# design.net
KiCad netlist of a schematic drawn in Altium Designer
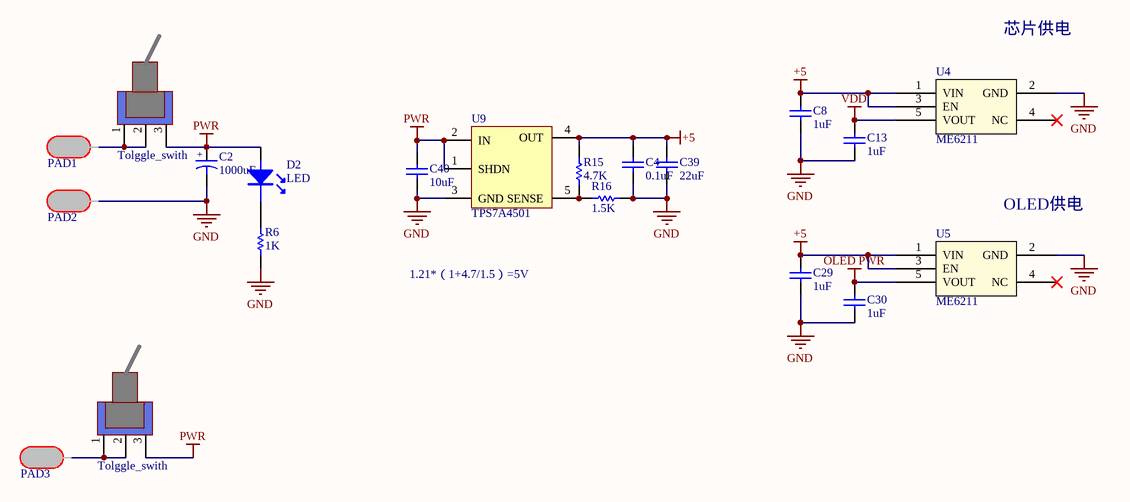
[diagram p0: 电源.SchDoc]

(export (version "E")
  (design (tool "Eeschema 10.0.6"))
  (components
    (comp (ref "C2")
      (value "1000uF")
      (footprint "CAP 10 x 12")
      (libsource (lib "LY御用集成库") (part "Cap_polar"))
    )
    (comp (ref "C4")
      (value "0.1uF")
      (footprint "0603_C")
      (description "Capacitor")
      (fields (field (name "PUBLISHER") "Altium Limited"))
      (libsource (lib "LY御用集成库") (part "CAP"))
    )
    (comp (ref "C8")
      (value "1uF")
      (footprint "0805_c")
      (description "Capacitor")
      (fields (field (name "PUBLISHER") "Altium Limited"))
      (libsource (lib "LY御用集成库") (part "CAP"))
    )
    (comp (ref "C13")
      (value "1uF")
      (footprint "0805_c")
      (description "Capacitor")
      (fields (field (name "PUBLISHER") "Altium Limited"))
      (libsource (lib "LY御用集成库") (part "CAP"))
    )
    (comp (ref "C29")
      (value "1uF")
      (footprint "0805_c")
      (description "Capacitor")
      (fields (field (name "PUBLISHER") "Altium Limited"))
      (libsource (lib "LY御用集成库") (part "CAP"))
    )
    (comp (ref "C30")
      (value "1uF")
      (footprint "0805_c")
      (description "Capacitor")
      (fields (field (name "PUBLISHER") "Altium Limited"))
      (libsource (lib "LY御用集成库") (part "CAP"))
    )
    (comp (ref "C39")
      (value "22uF")
      (footprint "0805_c")
      (description "Capacitor")
      (fields (field (name "PUBLISHER") "Altium Limited"))
      (libsource (lib "LY御用集成库") (part "CAP"))
    )
    (comp (ref "C40")
      (value "10uF")
      (footprint "0805_c")
      (description "Capacitor")
      (fields (field (name "PUBLISHER") "Altium Limited"))
      (libsource (lib "LY御用集成库") (part "CAP"))
    )
    (comp (ref "D2")
      (value "LED")
      (footprint "0603_LED")
      (description "LED 发光二极管")
      (libsource (lib "LY御用集成库") (part "LED"))
    )
    (comp (ref "Energy1")
      (value "Tolggle_swith")
      (footprint "TOGGLE SWICH STAND")
      (libsource (lib "LY御用集成库") (part "Tolggle_swith"))
    )
    (comp (ref "Energy2")
      (value "Tolggle_swith")
      (footprint "TOGGLE SWICH STAND")
      (libsource (lib "LY御用集成库") (part "Tolggle_swith"))
    )
    (comp (ref "PAD1") (value "PAD") (footprint "BIG PAD") (libsource (lib "LY御用集成库") (part "PAD")))
    (comp (ref "PAD2") (value "PAD") (footprint "BIG PAD") (libsource (lib "LY御用集成库") (part "PAD")))
    (comp (ref "PAD3") (value "PAD") (footprint "BIG PAD") (libsource (lib "LY御用集成库") (part "PAD")))
    (comp (ref "R6")
      (value "1K")
      (footprint "R0603")
      (description "Resistor")
      (fields (field (name "PUBLISHER") "Altium Limited"))
      (libsource (lib "LY御用集成库") (part "RES"))
    )
    (comp (ref "R15")
      (value "4.7K")
      (footprint "R0603")
      (description "Resistor")
      (fields (field (name "PUBLISHER") "Altium Limited"))
      (libsource (lib "LY御用集成库") (part "RES"))
    )
    (comp (ref "R16")
      (value "1.5K")
      (footprint "R0603")
      (description "Resistor")
      (fields (field (name "PUBLISHER") "Altium Limited"))
      (libsource (lib "LY御用集成库") (part "RES"))
    )
    (comp (ref "U4")
      (value "ME6211")
      (footprint "SOT23-5")
      (description "9uVRMS 150mA LDO")
      (libsource (lib "LY御用集成库") (part "ADP150AUJZ-1_8-R"))
    )
    (comp (ref "U5")
      (value "ME6211")
      (footprint "SOT23-5")
      (description "9uVRMS 150mA LDO")
      (libsource (lib "LY御用集成库") (part "ADP150AUJZ-1_8-R"))
    )
    (comp (ref "U9") (value "TPS7A4501") (footprint "SOT-6") (libsource (lib "mylib") (part "TL1963A")))
  )
  (nets
    (net (code "1") (name "+5") (class "Default")
      (node (ref "C29") (pin "2") (pinfunction "2_2") (pintype "passive"))
      (node (ref "C39") (pin "2") (pinfunction "2_2") (pintype "passive"))
      (node (ref "C4") (pin "2") (pinfunction "2_2") (pintype "passive"))
      (node (ref "C8") (pin "2") (pinfunction "2_2") (pintype "passive"))
      (node (ref "R15") (pin "2") (pinfunction "2_2") (pintype "passive"))
      (node (ref "U4") (pin "1") (pinfunction "VIN_1") (pintype "passive"))
      (node (ref "U4") (pin "3") (pinfunction "EN_3") (pintype "passive"))
      (node (ref "U5") (pin "1") (pinfunction "VIN_1") (pintype "passive"))
      (node (ref "U5") (pin "3") (pinfunction "EN_3") (pintype "passive"))
      (node (ref "U9") (pin "4") (pinfunction "OUT_4") (pintype "passive"))
    )
    (net (code "2") (name "GND") (class "Default")
      (node (ref "C13") (pin "1") (pinfunction "1_1") (pintype "passive"))
      (node (ref "C2") (pin "2") (pinfunction "2_2") (pintype "passive"))
      (node (ref "C29") (pin "1") (pinfunction "1_1") (pintype "passive"))
      (node (ref "C30") (pin "1") (pinfunction "1_1") (pintype "passive"))
      (node (ref "C39") (pin "1") (pinfunction "1_1") (pintype "passive"))
      (node (ref "C4") (pin "1") (pinfunction "1_1") (pintype "passive"))
      (node (ref "C40") (pin "1") (pinfunction "1_1") (pintype "passive"))
      (node (ref "C8") (pin "1") (pinfunction "1_1") (pintype "passive"))
      (node (ref "PAD2") (pin "1") (pinfunction "1_1") (pintype "passive"))
      (node (ref "R16") (pin "2") (pinfunction "2_2") (pintype "passive"))
      (node (ref "R6") (pin "1") (pinfunction "1_1") (pintype "passive"))
      (node (ref "U4") (pin "2") (pinfunction "GND_2") (pintype "passive"))
      (node (ref "U5") (pin "2") (pinfunction "GND_2") (pintype "passive"))
      (node (ref "U9") (pin "3") (pinfunction "GND_3") (pintype "passive"))
    )
    (net (code "3") (name "Net-(D2-K)") (class "Default")
      (node (ref "D2") (pin "2") (pinfunction "K_2") (pintype "passive"))
      (node (ref "R6") (pin "2") (pinfunction "2_2") (pintype "passive"))
    )
    (net (code "4") (name "Net-(Energy1-Pad1)") (class "Default")
      (node (ref "Energy1") (pin "1") (pintype "passive"))
      (node (ref "Energy1") (pin "2") (pintype "passive"))
      (node (ref "PAD1") (pin "1") (pinfunction "1_1") (pintype "passive"))
    )
    (net (code "5") (name "Net-(Energy2-Pad1)") (class "Default")
      (node (ref "Energy2") (pin "1") (pintype "passive"))
      (node (ref "Energy2") (pin "2") (pintype "passive"))
      (node (ref "PAD3") (pin "1") (pinfunction "1_1") (pintype "passive"))
    )
    (net (code "6") (name "Net-(U9-SENSE)") (class "Default")
      (node (ref "R15") (pin "1") (pinfunction "1_1") (pintype "passive"))
      (node (ref "R16") (pin "1") (pinfunction "1_1") (pintype "passive"))
      (node (ref "U9") (pin "5") (pinfunction "SENSE_5") (pintype "passive"))
    )
    (net (code "7") (name "OLED PWR") (class "Default")
      (node (ref "C30") (pin "2") (pinfunction "2_2") (pintype "passive"))
      (node (ref "U5") (pin "5") (pinfunction "VOUT_5") (pintype "passive"))
    )
    (net (code "8") (name "PWR") (class "Default")
      (node (ref "C2") (pin "1") (pinfunction "1_1") (pintype "passive"))
      (node (ref "C40") (pin "2") (pinfunction "2_2") (pintype "passive"))
      (node (ref "D2") (pin "1") (pinfunction "A_1") (pintype "passive"))
      (node (ref "Energy1") (pin "3") (pintype "passive"))
      (node (ref "Energy2") (pin "3") (pintype "passive"))
      (node (ref "U9") (pin "1") (pinfunction "SHDN_1") (pintype "passive"))
      (node (ref "U9") (pin "2") (pinfunction "IN_2") (pintype "passive"))
    )
    (net (code "9") (name "VDD") (class "Default")
      (node (ref "C13") (pin "2") (pinfunction "2_2") (pintype "passive"))
      (node (ref "U4") (pin "5") (pinfunction "VOUT_5") (pintype "passive"))
    )
    (net (code "10") (name "unconnected-(U4-NC-Pad4)") (class "Default")
      (node (ref "U4") (pin "4") (pinfunction "NC_4") (pintype "passive+no_connect"))
    )
    (net (code "11") (name "unconnected-(U5-NC-Pad4)") (class "Default")
      (node (ref "U5") (pin "4") (pinfunction "NC_4") (pintype "passive+no_connect"))
    )
  )
)
